# CarrierBoardPPower.net
KiCad netlist of a schematic drawn in Altium Designer
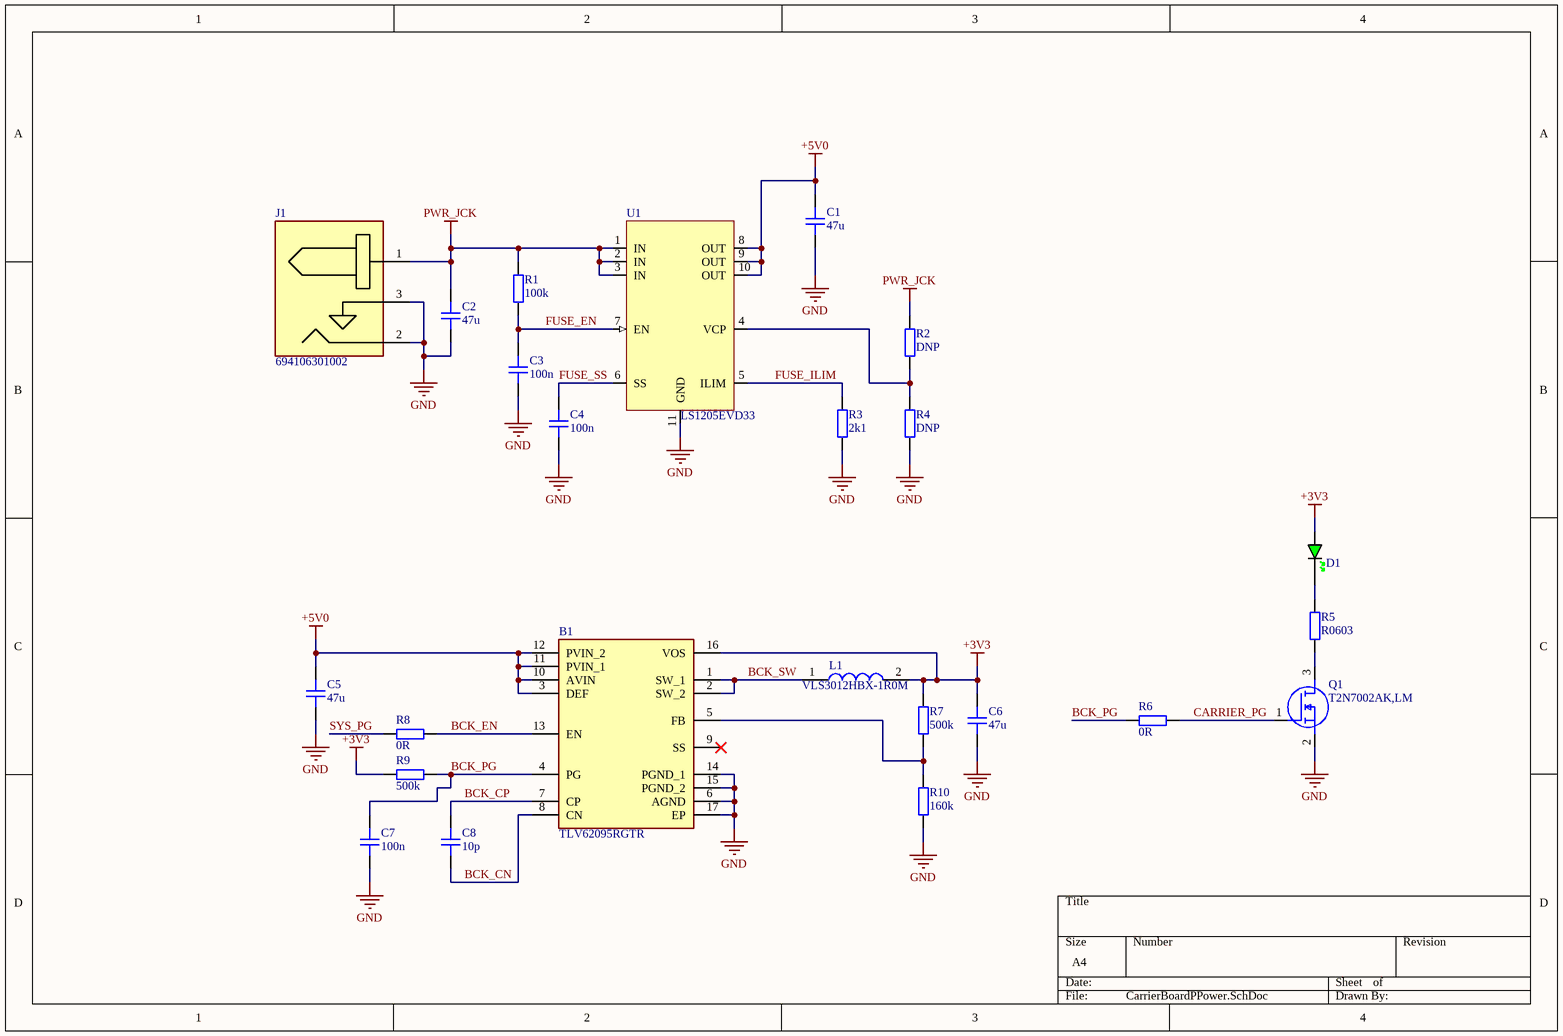
[diagram p0: CarrierBoardPPower.SchDoc]

(export (version "E")
  (design (tool "Eeschema 10.0.6"))
  (components
    (comp (ref "B1")
      (value "TLV62095RGTR")
      (footprint "QFN50P300X300X100-17N-D")
      (description "4A Synchronous Step Down Converter with DCS Control")
      (fields (field (name "MOUSER PART NUMBER") "595-TLV62095RGTR"))
      (libsource (lib "XC7Z030SCHLib") (part "TLV62095RGTR"))
    )
    (comp (ref "C1")
      (value "47u")
      (footprint "CAP_1210")
      (description "Capacitor SMD 1210")
      (libsource (lib "Schematic-Lib-PhilsLab") (part "CAP_1210"))
    )
    (comp (ref "C2")
      (value "47u")
      (footprint "CAP_1210")
      (description "Capacitor SMD 1210")
      (libsource (lib "Schematic-Lib-PhilsLab") (part "CAP_1210"))
    )
    (comp (ref "C3")
      (value "100n")
      (footprint "CAP_0402")
      (description "Capacitor SMD 0402")
      (libsource (lib "Schematic-Lib-PhilsLab") (part "CAP_0402"))
    )
    (comp (ref "C4")
      (value "100n")
      (footprint "CAP_0402")
      (description "Capacitor SMD 0402")
      (libsource (lib "Schematic-Lib-PhilsLab") (part "CAP_0402"))
    )
    (comp (ref "C5")
      (value "47u")
      (footprint "CAP_1210")
      (description "Capacitor SMD 1210")
      (libsource (lib "Schematic-Lib-PhilsLab") (part "CAP_1210"))
    )
    (comp (ref "C6")
      (value "47u")
      (footprint "CAP_1210")
      (description "Capacitor SMD 1210")
      (libsource (lib "Schematic-Lib-PhilsLab") (part "CAP_1210"))
    )
    (comp (ref "C7")
      (value "100n")
      (footprint "CAP_0402")
      (description "Capacitor SMD 0402")
      (libsource (lib "Schematic-Lib-PhilsLab") (part "CAP_0402"))
    )
    (comp (ref "C8")
      (value "10p")
      (footprint "CAP_0402")
      (description "Capacitor SMD 0402")
      (libsource (lib "Schematic-Lib-PhilsLab") (part "CAP_0402"))
    )
    (comp (ref "D1")
      (value "GREEN")
      (footprint "LED_0603_GREEN")
      (description "LED 0603 GREEN SMD")
      (libsource (lib "Schematic-Lib-PhilsLab") (part "LED_0603_GREEN"))
    )
    (comp (ref "J1")
      (value "694106301002")
      (footprint "CarrierBoardPCBLib:694106301002_1")
      (description "Connector")
      (fields (field (name "MOUSER PART NUMBER") "710-694106301002"))
      (libsource (lib "CarrierBoardSCHLib") (part "694106301002"))
    )
    (comp (ref "L1")
      (value "VLS3012HBX-1R0M")
      (footprint "XC7Z030PCBLib:VLS3012")
      (description "Inductor")
      (fields (field (name "MOUSER PART NUMBER") "810-VLS3012HBX-1R0M"))
      (libsource (lib "XC7Z030SCHLib") (part "VLS3012HBX-1R0M"))
    )
    (comp (ref "Q1")
      (value "T2N7002AK,LM")
      (footprint "Footprint-Lib-PhilsLab:TBAT54CLM")
      (description "MOSFET (N-Channel)")
      (fields (field (name "MOUSER PART NUMBER") "757-T2N7002AKLM"))
      (libsource (lib "Schematic-Lib-PhilsLab") (part "T2N7002AK,LM"))
    )
    (comp (ref "R1")
      (value "100k")
      (footprint "RES_0603")
      (description "Resistor SMD 0603")
      (libsource (lib "Schematic-Lib-PhilsLab") (part "RES_0603"))
    )
    (comp (ref "R2")
      (value "DNP")
      (footprint "RES_0603")
      (description "Resistor SMD 0603")
      (libsource (lib "Schematic-Lib-PhilsLab") (part "RES_0603"))
    )
    (comp (ref "R3")
      (value "2k1")
      (footprint "RES_0402")
      (description "Resistor SMD 0402")
      (libsource (lib "Schematic-Lib-PhilsLab") (part "RES_0402"))
    )
    (comp (ref "R4")
      (value "DNP")
      (footprint "RES_0603")
      (description "Resistor SMD 0603")
      (libsource (lib "Schematic-Lib-PhilsLab") (part "RES_0603"))
    )
    (comp (ref "R5")
      (value "R0603")
      (footprint "RES_0603")
      (description "Resistor SMD 0603")
      (libsource (lib "Schematic-Lib-PhilsLab") (part "RES_0603"))
    )
    (comp (ref "R6")
      (value "0R")
      (footprint "RES_0402")
      (description "Resistor SMD 0402")
      (libsource (lib "Schematic-Lib-PhilsLab") (part "RES_0402"))
    )
    (comp (ref "R7")
      (value "500k")
      (footprint "RES_0402")
      (description "Resistor SMD 0402")
      (libsource (lib "Schematic-Lib-PhilsLab") (part "RES_0402"))
    )
    (comp (ref "R8")
      (value "0R")
      (footprint "RES_0402")
      (description "Resistor SMD 0402")
      (libsource (lib "Schematic-Lib-PhilsLab") (part "RES_0402"))
    )
    (comp (ref "R9")
      (value "500k")
      (footprint "RES_0402")
      (description "Resistor SMD 0402")
      (libsource (lib "Schematic-Lib-PhilsLab") (part "RES_0402"))
    )
    (comp (ref "R10")
      (value "160k")
      (footprint "RES_0402")
      (description "Resistor SMD 0402")
      (libsource (lib "Schematic-Lib-PhilsLab") (part "RES_0402"))
    )
    (comp (ref "U1")
      (value "LS1205EVD33")
      (footprint "DFN3x3_10L")
      (description "18V, 5A eFuse with Programmable Current Limit and Output Voltage Clamp")
      (fields (field (name "MANUFACTURER") "Littelfuse"))
      (libsource (lib "Schematic-Lib-PhilsLab") (part "LS1205EVD33"))
    )
  )
  (nets
    (net (code "1") (name "+3V3") (class "Default")
      (node (ref "B1") (pin "16") (pinfunction "VOS_16") (pintype "passive"))
      (node (ref "C6") (pin "2") (pinfunction "2_2") (pintype "passive"))
      (node (ref "D1") (pin "A") (pinfunction "A_A") (pintype "passive"))
      (node (ref "L1") (pin "2") (pinfunction "2_2") (pintype "passive"))
      (node (ref "R7") (pin "2") (pinfunction "2_2") (pintype "passive"))
      (node (ref "R9") (pin "2") (pinfunction "2_2") (pintype "passive"))
    )
    (net (code "2") (name "+5V0") (class "Default")
      (node (ref "B1") (pin "10") (pinfunction "AVIN_10") (pintype "passive"))
      (node (ref "B1") (pin "11") (pinfunction "PVIN_1_11") (pintype "passive"))
      (node (ref "B1") (pin "12") (pinfunction "PVIN_2_12") (pintype "passive"))
      (node (ref "B1") (pin "3") (pinfunction "DEF_3") (pintype "passive"))
      (node (ref "C1") (pin "2") (pinfunction "2_2") (pintype "passive"))
      (node (ref "C5") (pin "2") (pinfunction "2_2") (pintype "passive"))
      (node (ref "U1") (pin "10") (pinfunction "OUT_10") (pintype "power_in"))
      (node (ref "U1") (pin "8") (pinfunction "OUT_8") (pintype "power_in"))
      (node (ref "U1") (pin "9") (pinfunction "OUT_9") (pintype "power_in"))
    )
    (net (code "3") (name "/BCK_CN") (class "Default")
      (node (ref "B1") (pin "8") (pinfunction "CN_8") (pintype "passive"))
      (node (ref "C8") (pin "1") (pinfunction "1_1") (pintype "passive"))
    )
    (net (code "4") (name "/BCK_CP") (class "Default")
      (node (ref "B1") (pin "7") (pinfunction "CP_7") (pintype "passive"))
      (node (ref "C8") (pin "2") (pinfunction "2_2") (pintype "passive"))
    )
    (net (code "5") (name "/BCK_EN") (class "Default")
      (node (ref "B1") (pin "13") (pinfunction "EN_13") (pintype "passive"))
      (node (ref "R8") (pin "1") (pinfunction "1_1") (pintype "passive"))
    )
    (net (code "6") (name "/BCK_PG") (class "Default")
      (node (ref "B1") (pin "4") (pinfunction "PG_4") (pintype "passive"))
      (node (ref "C7") (pin "2") (pinfunction "2_2") (pintype "passive"))
      (node (ref "R6") (pin "2") (pinfunction "2_2") (pintype "passive"))
      (node (ref "R9") (pin "1") (pinfunction "1_1") (pintype "passive"))
    )
    (net (code "7") (name "/BCK_SW") (class "Default")
      (node (ref "B1") (pin "1") (pinfunction "SW_1_1") (pintype "passive"))
      (node (ref "B1") (pin "2") (pinfunction "SW_2_2") (pintype "passive"))
      (node (ref "L1") (pin "1") (pinfunction "1_1") (pintype "passive"))
    )
    (net (code "8") (name "/CARRIER_PG") (class "Default")
      (node (ref "Q1") (pin "1") (pinfunction "G_1") (pintype "passive"))
      (node (ref "R6") (pin "1") (pinfunction "1_1") (pintype "passive"))
    )
    (net (code "9") (name "/FUSE_EN") (class "Default")
      (node (ref "C3") (pin "2") (pinfunction "2_2") (pintype "passive"))
      (node (ref "R1") (pin "1") (pinfunction "1_1") (pintype "passive"))
      (node (ref "U1") (pin "7") (pinfunction "EN_7") (pintype "input"))
    )
    (net (code "10") (name "/FUSE_ILIM") (class "Default")
      (node (ref "R3") (pin "2") (pinfunction "2_2") (pintype "passive"))
      (node (ref "U1") (pin "5") (pinfunction "ILIM_5") (pintype "passive"))
    )
    (net (code "11") (name "/FUSE_SS") (class "Default")
      (node (ref "C4") (pin "2") (pinfunction "2_2") (pintype "passive"))
      (node (ref "U1") (pin "6") (pinfunction "SS_6") (pintype "passive"))
    )
    (net (code "12") (name "/SYS_PG") (class "Default")
      (node (ref "R8") (pin "2") (pinfunction "2_2") (pintype "passive"))
    )
    (net (code "13") (name "GND") (class "Default")
      (node (ref "B1") (pin "14") (pinfunction "PGND_1_14") (pintype "passive"))
      (node (ref "B1") (pin "15") (pinfunction "PGND_2_15") (pintype "passive"))
      (node (ref "B1") (pin "17") (pinfunction "EP_17") (pintype "passive"))
      (node (ref "B1") (pin "6") (pinfunction "AGND_6") (pintype "passive"))
      (node (ref "C1") (pin "1") (pinfunction "1_1") (pintype "passive"))
      (node (ref "C2") (pin "1") (pinfunction "1_1") (pintype "passive"))
      (node (ref "C3") (pin "1") (pinfunction "1_1") (pintype "passive"))
      (node (ref "C4") (pin "1") (pinfunction "1_1") (pintype "passive"))
      (node (ref "C5") (pin "1") (pinfunction "1_1") (pintype "passive"))
      (node (ref "C6") (pin "1") (pinfunction "1_1") (pintype "passive"))
      (node (ref "C7") (pin "1") (pinfunction "1_1") (pintype "passive"))
      (node (ref "J1") (pin "2") (pintype "passive"))
      (node (ref "J1") (pin "3") (pintype "passive"))
      (node (ref "Q1") (pin "2") (pinfunction "S_2") (pintype "passive"))
      (node (ref "R10") (pin "1") (pinfunction "1_1") (pintype "passive"))
      (node (ref "R3") (pin "1") (pinfunction "1_1") (pintype "passive"))
      (node (ref "R4") (pin "1") (pinfunction "1_1") (pintype "passive"))
      (node (ref "U1") (pin "11") (pinfunction "GND_11") (pintype "power_in"))
    )
    (net (code "14") (name "Net-(B1-FB)") (class "Default")
      (node (ref "B1") (pin "5") (pinfunction "FB_5") (pintype "passive"))
      (node (ref "R10") (pin "2") (pinfunction "2_2") (pintype "passive"))
      (node (ref "R7") (pin "1") (pinfunction "1_1") (pintype "passive"))
    )
    (net (code "15") (name "Net-(D1-PadK)") (class "Default")
      (node (ref "D1") (pin "K") (pinfunction "K_K") (pintype "passive"))
      (node (ref "R5") (pin "2") (pinfunction "2_2") (pintype "passive"))
    )
    (net (code "16") (name "Net-(Q1-D)") (class "Default")
      (node (ref "Q1") (pin "3") (pinfunction "D_3") (pintype "passive"))
      (node (ref "R5") (pin "1") (pinfunction "1_1") (pintype "passive"))
    )
    (net (code "17") (name "Net-(U1-VCP)") (class "Default")
      (node (ref "R2") (pin "1") (pinfunction "1_1") (pintype "passive"))
      (node (ref "R4") (pin "2") (pinfunction "2_2") (pintype "passive"))
      (node (ref "U1") (pin "4") (pinfunction "VCP_4") (pintype "passive"))
    )
    (net (code "18") (name "PWR_JCK") (class "Default")
      (node (ref "C2") (pin "2") (pinfunction "2_2") (pintype "passive"))
      (node (ref "J1") (pin "1") (pintype "passive"))
      (node (ref "R1") (pin "2") (pinfunction "2_2") (pintype "passive"))
      (node (ref "R2") (pin "2") (pinfunction "2_2") (pintype "passive"))
      (node (ref "U1") (pin "1") (pinfunction "IN_1") (pintype "power_in"))
      (node (ref "U1") (pin "2") (pinfunction "IN_2") (pintype "power_in"))
      (node (ref "U1") (pin "3") (pinfunction "IN_3") (pintype "power_in"))
    )
    (net (code "19") (name "unconnected-(B1-SS-Pad9)") (class "Default")
      (node (ref "B1") (pin "9") (pinfunction "SS_9") (pintype "passive+no_connect"))
    )
  )
)
